# VehicleDriverSchematic.net
KiCad netlist of a schematic drawn in EAGLE
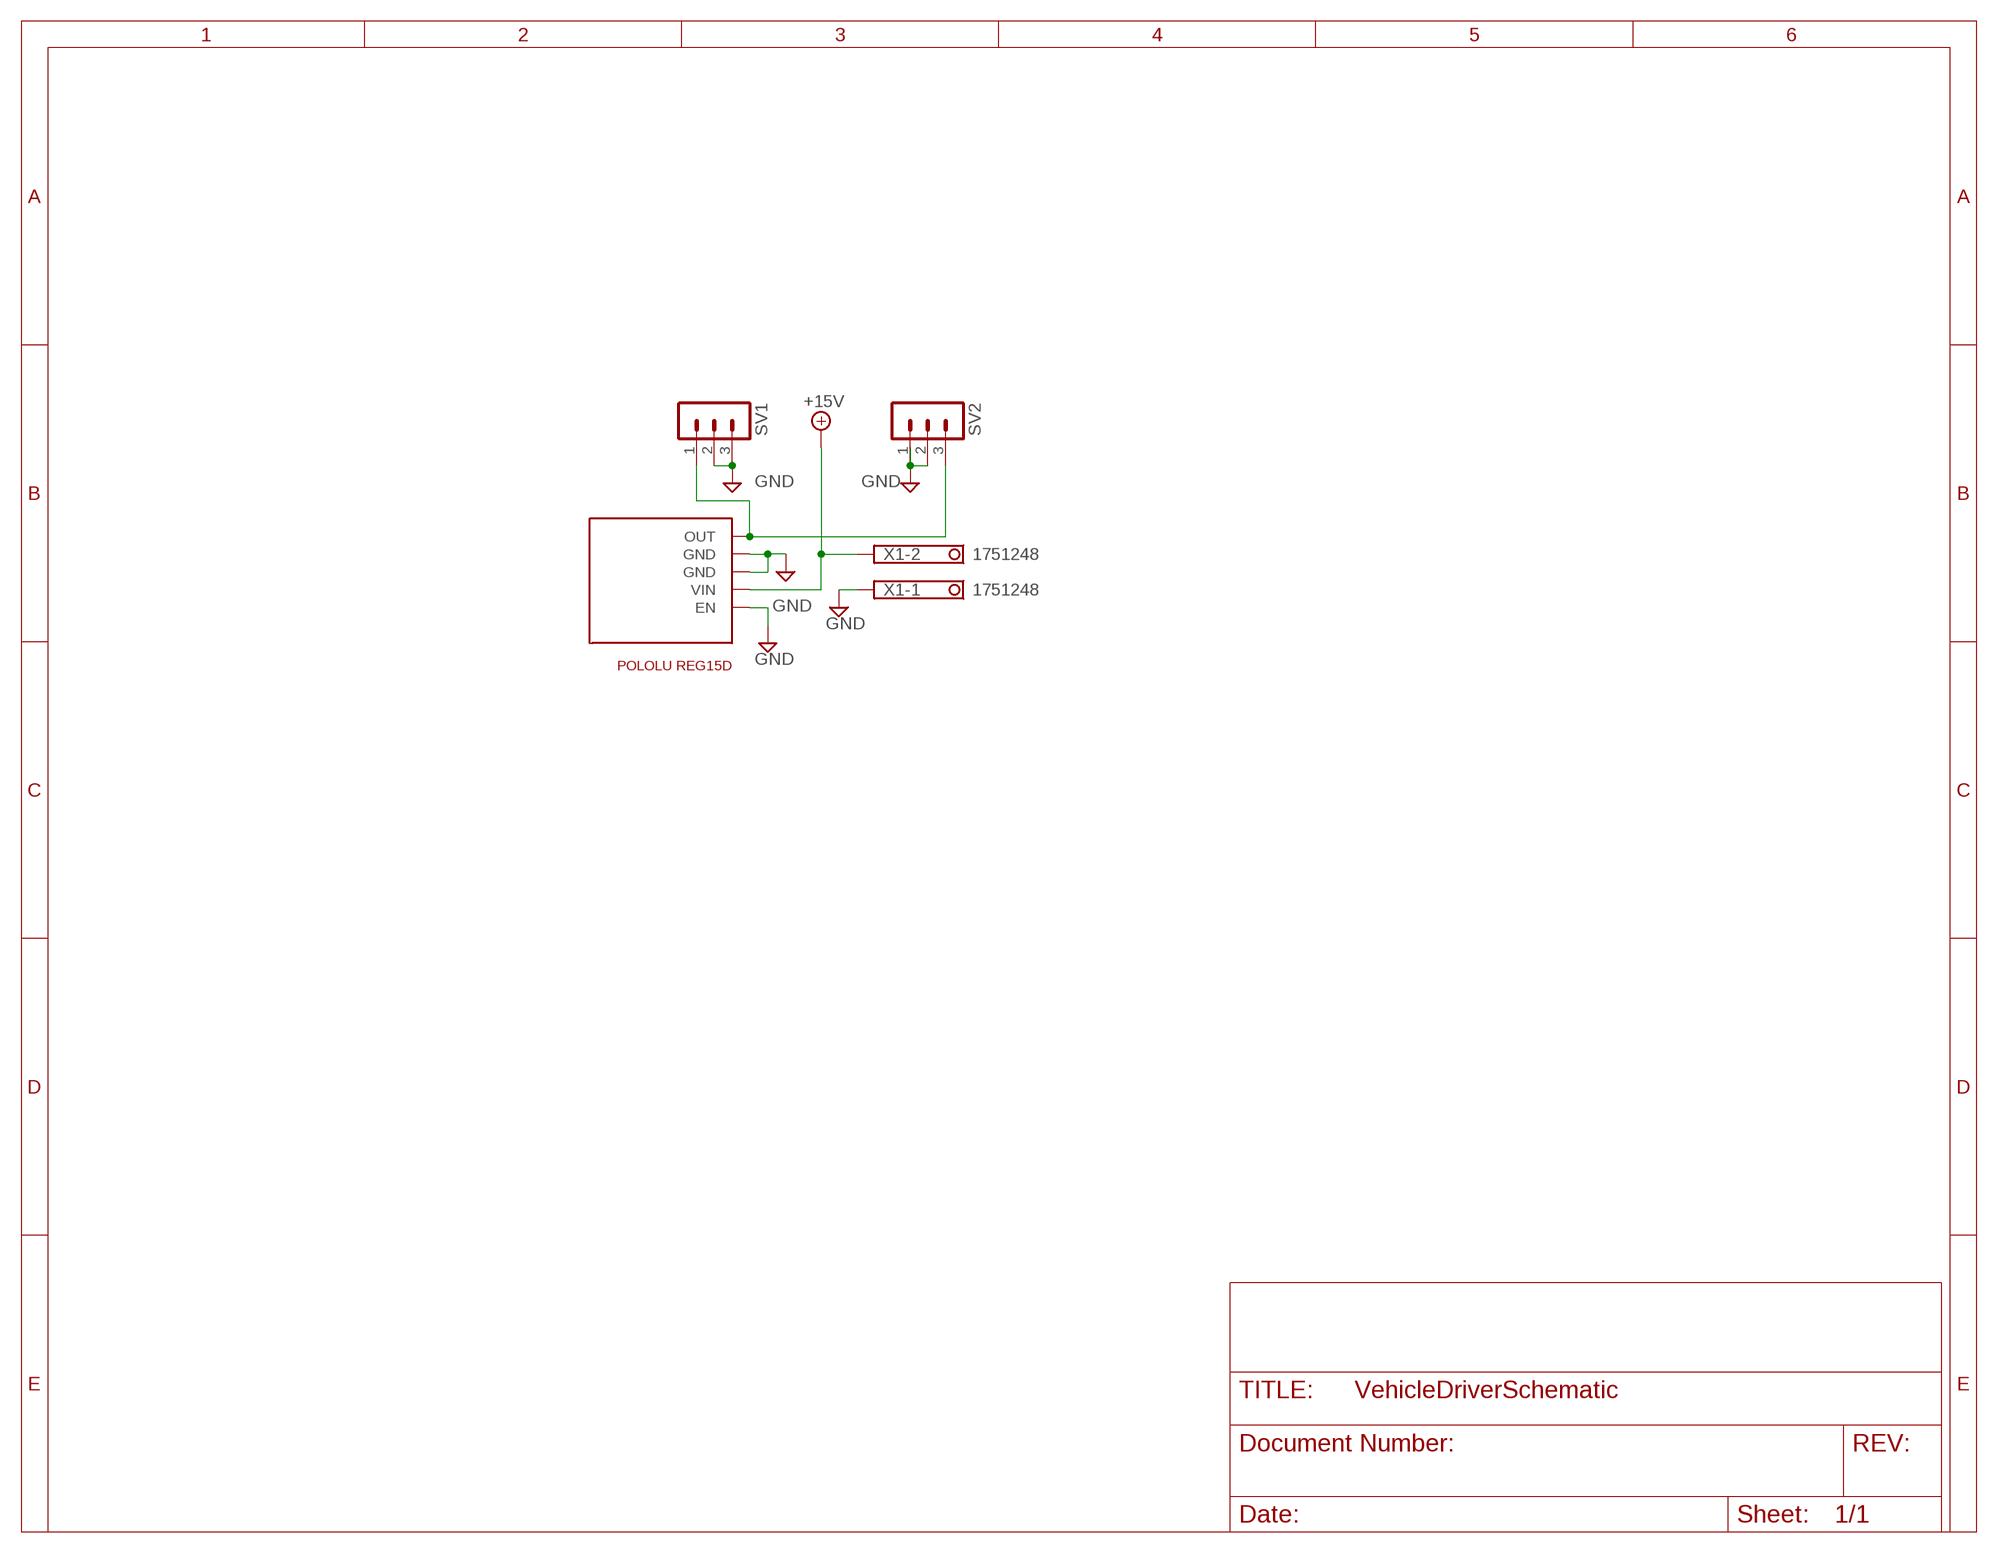
[diagram p0: schematic, sheet 1]

(export (version "E")
  (design (tool "Eeschema 10.0.6"))
  (components
    (comp (ref "SV1")
      (value "MA03-1")
      (footprint "eagle-import:MA03-1")
      (libsource (lib "eagle-import") (part "MA03-1"))
    )
    (comp (ref "SV2")
      (value "MA03-1")
      (footprint "eagle-import:MA03-1")
      (libsource (lib "eagle-import") (part "MA03-1"))
    )
    (comp (ref "U$1")
      (value "POLOLU_REG15D")
      (footprint "eagle-import:POLOLU_REG15D")
      (libsource (lib "eagle-import") (part "POLOLU_REG15D"))
    )
    (comp (ref "X1")
      (value "1751248")
      (footprint "eagle-import:1751248")
      (libsource (lib "eagle-import") (part "1751248"))
    )
  )
  (nets
    (net (code "1") (name "+15V") (class "Default")
      (node (ref "U$1") (pin "VIN") (pinfunction "VIN_VIN") (pintype "power_in"))
      (node (ref "X1") (pin "2") (pinfunction "K_2") (pintype "passive"))
    )
    (net (code "2") (name "GND") (class "Default")
      (node (ref "SV1") (pin "2") (pinfunction "2_2") (pintype "passive"))
      (node (ref "SV1") (pin "3") (pinfunction "3_3") (pintype "passive"))
      (node (ref "SV2") (pin "1") (pinfunction "1_1") (pintype "passive"))
      (node (ref "SV2") (pin "2") (pinfunction "2_2") (pintype "passive"))
      (node (ref "U$1") (pin "EN") (pinfunction "EN_EN") (pintype "input"))
      (node (ref "U$1") (pin "GND") (pinfunction "GND_GND") (pintype "power_in"))
      (node (ref "U$1") (pin "GND@1") (pinfunction "GND_GND@1") (pintype "power_in"))
      (node (ref "X1") (pin "1") (pinfunction "K_1") (pintype "passive"))
    )
    (net (code "3") (name "Net-(SV1-Pad1)") (class "Default")
      (node (ref "SV1") (pin "1") (pinfunction "1_1") (pintype "passive"))
      (node (ref "SV2") (pin "3") (pinfunction "3_3") (pintype "passive"))
      (node (ref "U$1") (pin "OUT") (pinfunction "OUT_OUT") (pintype "output"))
    )
  )
)
